# PSU.net
KiCad netlist of a schematic drawn in Altium Designer
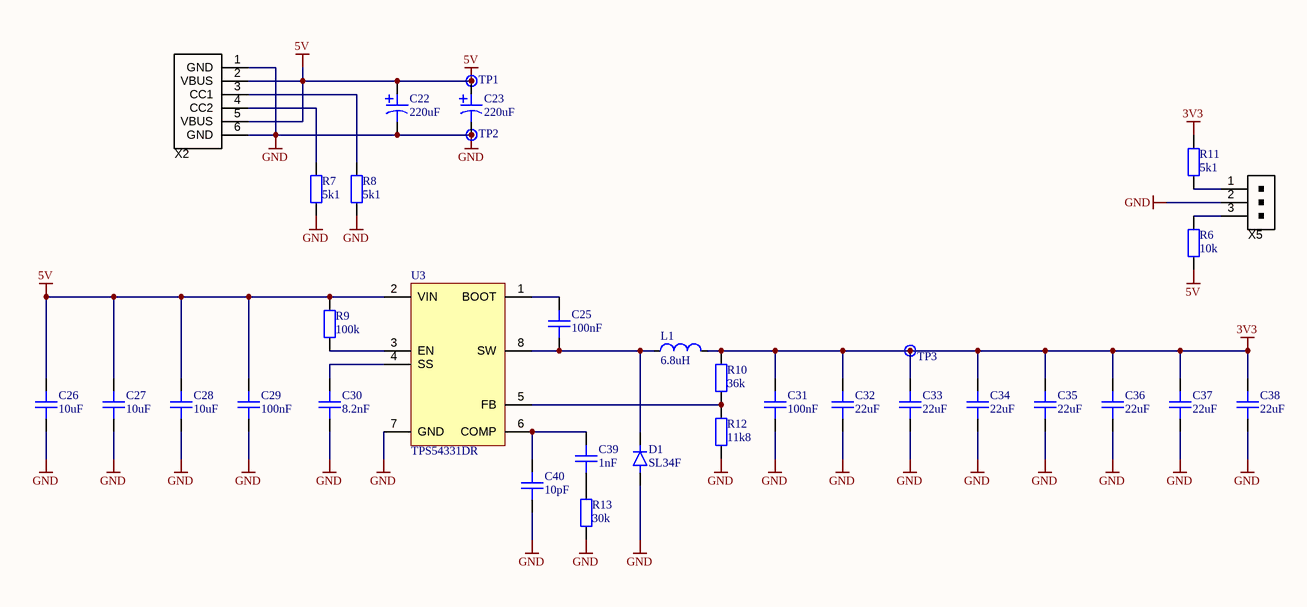
[diagram p0: PSU.SchDoc]

(export (version "E")
  (design (tool "Eeschema 10.0.6"))
  (components
    (comp (ref "C22")
      (value "220uF")
      (footprint "CAP-TANT-D")
      (description "Capacitor Polar")
      (libsource (lib "MasterLib") (part "CAP - TANT - D"))
    )
    (comp (ref "C23")
      (value "220uF")
      (footprint "CAP-TANT-D")
      (description "Capacitor Polar")
      (libsource (lib "MasterLib") (part "CAP - TANT - D"))
    )
    (comp (ref "C25")
      (value "100nF")
      (footprint "CAP-0603")
      (description "Capacitor Non-Polar")
      (libsource (lib "MasterLib") (part "CAP - 0603"))
    )
    (comp (ref "C26")
      (value "10uF")
      (footprint "CAP-0805")
      (description "Capacitor Non-Polar")
      (libsource (lib "MasterLib") (part "CAP - 0805"))
    )
    (comp (ref "C27")
      (value "10uF")
      (footprint "CAP-0805")
      (description "Capacitor Non-Polar")
      (libsource (lib "MasterLib") (part "CAP - 0805"))
    )
    (comp (ref "C28")
      (value "10uF")
      (footprint "CAP-0805")
      (description "Capacitor Non-Polar")
      (libsource (lib "MasterLib") (part "CAP - 0805"))
    )
    (comp (ref "C29")
      (value "100nF")
      (footprint "CAP-0805")
      (description "Capacitor Non-Polar")
      (libsource (lib "MasterLib") (part "CAP - 0805"))
    )
    (comp (ref "C30")
      (value "8.2nF")
      (footprint "CAP-0603")
      (description "Capacitor Non-Polar")
      (libsource (lib "MasterLib") (part "CAP - 0603"))
    )
    (comp (ref "C31")
      (value "100nF")
      (footprint "CAP-0805")
      (description "Capacitor Non-Polar")
      (libsource (lib "MasterLib") (part "CAP - 0805"))
    )
    (comp (ref "C32")
      (value "22uF")
      (footprint "CAP-0805")
      (description "Capacitor Non-Polar")
      (libsource (lib "MasterLib") (part "CAP - 0805"))
    )
    (comp (ref "C33")
      (value "22uF")
      (footprint "CAP-0805")
      (description "Capacitor Non-Polar")
      (libsource (lib "MasterLib") (part "CAP - 0805"))
    )
    (comp (ref "C34")
      (value "22uF")
      (footprint "CAP-0805")
      (description "Capacitor Non-Polar")
      (libsource (lib "MasterLib") (part "CAP - 0805"))
    )
    (comp (ref "C35")
      (value "22uF")
      (footprint "CAP-0805")
      (description "Capacitor Non-Polar")
      (libsource (lib "MasterLib") (part "CAP - 0805"))
    )
    (comp (ref "C36")
      (value "22uF")
      (footprint "CAP-0805")
      (description "Capacitor Non-Polar")
      (libsource (lib "MasterLib") (part "CAP - 0805"))
    )
    (comp (ref "C37")
      (value "22uF")
      (footprint "CAP-0805")
      (description "Capacitor Non-Polar")
      (libsource (lib "MasterLib") (part "CAP - 0805"))
    )
    (comp (ref "C38")
      (value "22uF")
      (footprint "CAP-0805")
      (description "Capacitor Non-Polar")
      (libsource (lib "MasterLib") (part "CAP - 0805"))
    )
    (comp (ref "C39")
      (value "1nF")
      (footprint "CAP-0603")
      (description "Capacitor Non-Polar")
      (libsource (lib "MasterLib") (part "CAP - 0603"))
    )
    (comp (ref "C40")
      (value "10pF")
      (footprint "CAP-0603")
      (description "Capacitor Non-Polar")
      (libsource (lib "MasterLib") (part "CAP - 0603"))
    )
    (comp (ref "D1")
      (value "SL34F")
      (footprint "D-SMAF")
      (description "3A 600V DO-214AB RECT.SUP.FAST trr<35ns ES3J")
      (libsource (lib "MasterLib") (part "D - SL34F"))
    )
    (comp (ref "L1")
      (value "6.8uH")
      (footprint "IND-SMD-6.5x6.5mm")
      (description "12.7x12.7mm choke inductor")
      (libsource (lib "MasterLib") (part "IND - SMD"))
    )
    (comp (ref "R6")
      (value "10k")
      (footprint "RES-0603")
      (description "Resistor")
      (libsource (lib "MasterLib") (part "RES - 0603"))
    )
    (comp (ref "R7")
      (value "5k1")
      (footprint "RES-0603")
      (description "Resistor")
      (libsource (lib "") (part "RES - 0603_1"))
    )
    (comp (ref "R8")
      (value "5k1")
      (footprint "RES-0603")
      (description "Resistor")
      (libsource (lib "") (part "RES - 0603_1"))
    )
    (comp (ref "R9")
      (value "100k")
      (footprint "RES-0603")
      (description "Resistor")
      (libsource (lib "MasterLib") (part "RES - 0603"))
    )
    (comp (ref "R10")
      (value "36k")
      (footprint "RES-0603")
      (description "Resistor")
      (libsource (lib "") (part "RES - 0603_1"))
    )
    (comp (ref "R11")
      (value "5k1")
      (footprint "RES-0603")
      (description "Resistor")
      (libsource (lib "") (part "RES - 0603_1"))
    )
    (comp (ref "R12")
      (value "11k8")
      (footprint "RES-0603")
      (description "Resistor")
      (libsource (lib "") (part "RES - 0603_1"))
    )
    (comp (ref "R13")
      (value "30k")
      (footprint "RES-0603")
      (description "Resistor")
      (libsource (lib "") (part "RES - 0603_1"))
    )
    (comp (ref "TP1")
      (value "MISC - Testpoint SMT")
      (footprint "MISC-TESTPOINT-SMT")
      (description "SMT testpoint")
      (libsource (lib "MasterLib") (part "MISC - Testpoint SMT"))
    )
    (comp (ref "TP2")
      (value "MISC - Testpoint SMT")
      (footprint "MISC-TESTPOINT-SMT")
      (description "SMT testpoint")
      (libsource (lib "MasterLib") (part "MISC - Testpoint SMT"))
    )
    (comp (ref "TP3")
      (value "MISC - Testpoint SMT")
      (footprint "MISC-TESTPOINT-SMT")
      (description "SMT testpoint")
      (libsource (lib "MasterLib") (part "MISC - Testpoint SMT"))
    )
    (comp (ref "U3")
      (value "TPS54331DR")
      (footprint "IC-SOIC-8")
      (description "3-A, 28-V Input, Step Down DC-DC Converter With Eco-mode")
      (libsource (lib "MasterLib") (part "IC - TPS54331"))
    )
    (comp (ref "X2")
      (value "CONN - USB-C")
      (footprint "CONN-USB-C")
      (description "USB-C connector, power supply only")
      (libsource (lib "MasterLib") (part "CONN - USB-C"))
    )
    (comp (ref "X5")
      (value "CONN - 3P - THT-JST 1.5mm")
      (footprint "CONN-3P-THT-JST 1.5mm")
      (description "1x3 pin header")
      (libsource (lib "MasterLib") (part "CONN - 3P - THT-JST 1.5mm"))
    )
  )
  (nets
    (net (code "1") (name "3V3") (class "Default")
      (node (ref "C31") (pin "2") (pinfunction "2_2") (pintype "passive"))
      (node (ref "C32") (pin "2") (pinfunction "2_2") (pintype "passive"))
      (node (ref "C33") (pin "2") (pinfunction "2_2") (pintype "passive"))
      (node (ref "C34") (pin "2") (pinfunction "2_2") (pintype "passive"))
      (node (ref "C35") (pin "2") (pinfunction "2_2") (pintype "passive"))
      (node (ref "C36") (pin "2") (pinfunction "2_2") (pintype "passive"))
      (node (ref "C37") (pin "2") (pinfunction "2_2") (pintype "passive"))
      (node (ref "C38") (pin "2") (pinfunction "2_2") (pintype "passive"))
      (node (ref "L1") (pin "2") (pinfunction "2_2") (pintype "passive"))
      (node (ref "R10") (pin "2") (pinfunction "2_2") (pintype "passive"))
      (node (ref "R11") (pin "2") (pinfunction "2_2") (pintype "passive"))
      (node (ref "TP3") (pin "1") (pinfunction "1_1") (pintype "passive"))
    )
    (net (code "2") (name "5V") (class "Default")
      (node (ref "C22") (pin "2") (pinfunction "2_2") (pintype "passive"))
      (node (ref "C23") (pin "2") (pinfunction "2_2") (pintype "passive"))
      (node (ref "C26") (pin "2") (pinfunction "2_2") (pintype "passive"))
      (node (ref "C27") (pin "2") (pinfunction "2_2") (pintype "passive"))
      (node (ref "C28") (pin "2") (pinfunction "2_2") (pintype "passive"))
      (node (ref "C29") (pin "2") (pinfunction "2_2") (pintype "passive"))
      (node (ref "R6") (pin "2") (pinfunction "2_2") (pintype "passive"))
      (node (ref "R9") (pin "1") (pinfunction "1_1") (pintype "passive"))
      (node (ref "TP1") (pin "1") (pinfunction "1_1") (pintype "passive"))
      (node (ref "U3") (pin "2") (pinfunction "VIN_2") (pintype "passive"))
      (node (ref "X2") (pin "2") (pinfunction "VBUS_2") (pintype "passive"))
      (node (ref "X2") (pin "5") (pinfunction "VBUS_5") (pintype "passive"))
    )
    (net (code "3") (name "GND") (class "Default")
      (node (ref "C22") (pin "1") (pinfunction "1_1") (pintype "passive"))
      (node (ref "C23") (pin "1") (pinfunction "1_1") (pintype "passive"))
      (node (ref "C26") (pin "1") (pinfunction "1_1") (pintype "passive"))
      (node (ref "C27") (pin "1") (pinfunction "1_1") (pintype "passive"))
      (node (ref "C28") (pin "1") (pinfunction "1_1") (pintype "passive"))
      (node (ref "C29") (pin "1") (pinfunction "1_1") (pintype "passive"))
      (node (ref "C30") (pin "1") (pinfunction "1_1") (pintype "passive"))
      (node (ref "C31") (pin "1") (pinfunction "1_1") (pintype "passive"))
      (node (ref "C32") (pin "1") (pinfunction "1_1") (pintype "passive"))
      (node (ref "C33") (pin "1") (pinfunction "1_1") (pintype "passive"))
      (node (ref "C34") (pin "1") (pinfunction "1_1") (pintype "passive"))
      (node (ref "C35") (pin "1") (pinfunction "1_1") (pintype "passive"))
      (node (ref "C36") (pin "1") (pinfunction "1_1") (pintype "passive"))
      (node (ref "C37") (pin "1") (pinfunction "1_1") (pintype "passive"))
      (node (ref "C38") (pin "1") (pinfunction "1_1") (pintype "passive"))
      (node (ref "C40") (pin "1") (pinfunction "1_1") (pintype "passive"))
      (node (ref "D1") (pin "1") (pinfunction "1_1") (pintype "passive"))
      (node (ref "R12") (pin "1") (pinfunction "1_1") (pintype "passive"))
      (node (ref "R13") (pin "1") (pinfunction "1_1") (pintype "passive"))
      (node (ref "R7") (pin "1") (pinfunction "1_1") (pintype "passive"))
      (node (ref "R8") (pin "1") (pinfunction "1_1") (pintype "passive"))
      (node (ref "TP2") (pin "1") (pinfunction "1_1") (pintype "passive"))
      (node (ref "U3") (pin "7") (pinfunction "GND_7") (pintype "passive"))
      (node (ref "X2") (pin "1") (pinfunction "GND_1") (pintype "passive"))
      (node (ref "X2") (pin "6") (pinfunction "GND_6") (pintype "passive"))
      (node (ref "X5") (pin "2") (pinfunction "2_2") (pintype "passive"))
    )
    (net (code "4") (name "Net-(C39-Pad1)") (class "Default")
      (node (ref "C39") (pin "1") (pinfunction "1_1") (pintype "passive"))
      (node (ref "R13") (pin "2") (pinfunction "2_2") (pintype "passive"))
    )
    (net (code "5") (name "Net-(R6-Pad1)") (class "Default")
      (node (ref "R6") (pin "1") (pinfunction "1_1") (pintype "passive"))
      (node (ref "X5") (pin "3") (pinfunction "3_3") (pintype "passive"))
    )
    (net (code "6") (name "Net-(R11-Pad1)") (class "Default")
      (node (ref "R11") (pin "1") (pinfunction "1_1") (pintype "passive"))
      (node (ref "X5") (pin "1") (pinfunction "1_1") (pintype "passive"))
    )
    (net (code "7") (name "Net-(U3-BOOT)") (class "Default")
      (node (ref "C25") (pin "2") (pinfunction "2_2") (pintype "passive"))
      (node (ref "U3") (pin "1") (pinfunction "BOOT_1") (pintype "passive"))
    )
    (net (code "8") (name "Net-(U3-COMP)") (class "Default")
      (node (ref "C39") (pin "2") (pinfunction "2_2") (pintype "passive"))
      (node (ref "C40") (pin "2") (pinfunction "2_2") (pintype "passive"))
      (node (ref "U3") (pin "6") (pinfunction "COMP_6") (pintype "passive"))
    )
    (net (code "9") (name "Net-(U3-EN)") (class "Default")
      (node (ref "R9") (pin "2") (pinfunction "2_2") (pintype "passive"))
      (node (ref "U3") (pin "3") (pinfunction "EN_3") (pintype "passive"))
    )
    (net (code "10") (name "Net-(U3-FB)") (class "Default")
      (node (ref "R10") (pin "1") (pinfunction "1_1") (pintype "passive"))
      (node (ref "R12") (pin "2") (pinfunction "2_2") (pintype "passive"))
      (node (ref "U3") (pin "5") (pinfunction "FB_5") (pintype "passive"))
    )
    (net (code "11") (name "Net-(U3-SS)") (class "Default")
      (node (ref "C30") (pin "2") (pinfunction "2_2") (pintype "passive"))
      (node (ref "U3") (pin "4") (pinfunction "SS_4") (pintype "passive"))
    )
    (net (code "12") (name "Net-(U3-SW)") (class "Default")
      (node (ref "C25") (pin "1") (pinfunction "1_1") (pintype "passive"))
      (node (ref "D1") (pin "2") (pinfunction "2_2") (pintype "passive"))
      (node (ref "L1") (pin "1") (pinfunction "1_1") (pintype "passive"))
      (node (ref "U3") (pin "8") (pinfunction "SW_8") (pintype "passive"))
    )
    (net (code "13") (name "Net-(X2-CC1)") (class "Default")
      (node (ref "R8") (pin "2") (pinfunction "2_2") (pintype "passive"))
      (node (ref "X2") (pin "3") (pinfunction "CC1_3") (pintype "passive"))
    )
    (net (code "14") (name "Net-(X2-CC2)") (class "Default")
      (node (ref "R7") (pin "2") (pinfunction "2_2") (pintype "passive"))
      (node (ref "X2") (pin "4") (pinfunction "CC2_4") (pintype "passive"))
    )
  )
)
